# TPS62082.net
KiCad netlist of a schematic drawn in Altium Designer
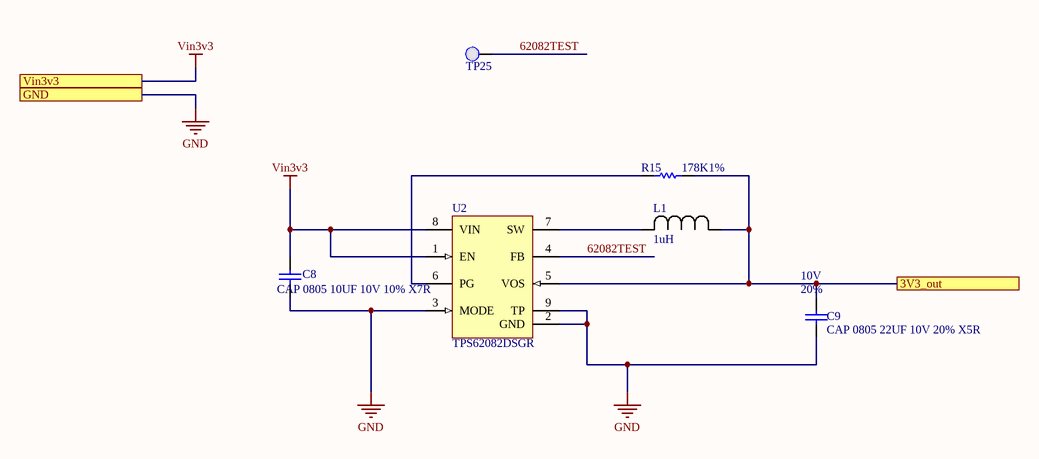
[diagram p0: TPS62082.SchDoc]

(export (version "E")
  (design (tool "Eeschema 10.0.6"))
  (components
    (comp (ref "C8")
      (value "CAP 0805 10UF 10V 10% X7R")
      (footprint "0805_CAP")
      (description "Capacitor Surface Mount 0805 Footprint 10UF 10V 10% Tolerance Ceramic X7R")
      (fields (field (name "MANUFACTURER") "Various"))
      (libsource (lib "University of Pennsylvania (ESE Labs)") (part "cap"))
    )
    (comp (ref "C9")
      (value "CAP 0805 22UF 10V 20% X5R")
      (footprint "0805_CAP_60H")
      (description "Capacitor Surface Mount 0805 Footprint 22UF 10V 20% Tolerance Ceramic X5R")
      (fields
        (field (name "MANUFACTURER") "Various")
        (field (name "TOLERANCE") "20%")
        (field (name "VOLTAGE") "10V")
      )
      (libsource (lib "University of Pennsylvania (ESE Labs)") (part "cap"))
    )
    (comp (ref "L1")
      (value "1uH")
      (footprint "IND_16100_WRE")
      (description "No Description Available")
      (libsource (lib "Schlib1") (part "744316100"))
    )
    (comp (ref "R15")
      (value "178K")
      (footprint "0402_RES")
      (description "Resistor Surface Mount, 178K Ohms, 0402 Footprint, 1% Tolerance 0.063W")
      (fields
        (field (name "MANUFACTURER") "Various")
        (field (name "TOLERANCE") "1%")
        (field (name "Comment") "RES 0402 178K 1%")
      )
      (libsource (lib "University of Pennsylvania (ESE Labs)") (part "res"))
    )
    (comp (ref "TP25")
      (value "Test Point 0.1\"")
      (footprint "Test Point 0.1\"-Footprint-1")
      (libsource (lib "University of Pennsylvania (ESE Labs)") (part "Test Point 0.1{dblquote}-Symbol-1"))
    )
    (comp (ref "U2")
      (value "TPS62082DSGR")
      (footprint "DSG0008A_V")
      (fields (field (name "MANUFACTURER") "Texas Instruments"))
      (libsource (lib "Schlib1") (part "CMP-0323-00344-3"))
    )
  )
  (nets
    (net (code "1") (name "/3V3_out") (class "Default")
      (node (ref "C9") (pin "2") (pinfunction "2_2") (pintype "passive"))
      (node (ref "L1") (pin "1") (pinfunction "1_1") (pintype "passive"))
      (node (ref "R15") (pin "2") (pinfunction "2_2") (pintype "passive"))
      (node (ref "U2") (pin "5") (pinfunction "VOS_5") (pintype "input"))
    )
    (net (code "2") (name "/62082TEST") (class "Default")
      (node (ref "TP25") (pin "1") (pinfunction "PAD_1") (pintype "passive"))
      (node (ref "U2") (pin "4") (pinfunction "FB_4") (pintype "passive"))
    )
    (net (code "3") (name "GND") (class "Default")
      (node (ref "C8") (pin "1") (pinfunction "1_1") (pintype "passive"))
      (node (ref "C9") (pin "1") (pinfunction "1_1") (pintype "passive"))
      (node (ref "U2") (pin "2") (pinfunction "GND_2") (pintype "power_in"))
      (node (ref "U2") (pin "3") (pinfunction "MODE_3") (pintype "input"))
      (node (ref "U2") (pin "9") (pinfunction "TP_9") (pintype "power_in"))
    )
    (net (code "4") (name "Net-(U2-PG)") (class "Default")
      (node (ref "R15") (pin "1") (pinfunction "1_1") (pintype "passive"))
      (node (ref "U2") (pin "6") (pinfunction "PG_6") (pintype "tri_state"))
    )
    (net (code "5") (name "Net-(U2-SW)") (class "Default")
      (node (ref "L1") (pin "2") (pinfunction "2_2") (pintype "passive"))
      (node (ref "U2") (pin "7") (pinfunction "SW_7") (pintype "power_in"))
    )
    (net (code "6") (name "Vin3v3") (class "Default")
      (node (ref "C8") (pin "2") (pinfunction "2_2") (pintype "passive"))
      (node (ref "U2") (pin "1") (pinfunction "EN_1") (pintype "input"))
      (node (ref "U2") (pin "8") (pinfunction "VIN_8") (pintype "power_in"))
    )
  )
)
